# Sheet1.net
KiCad netlist of a schematic drawn in Altium Designer
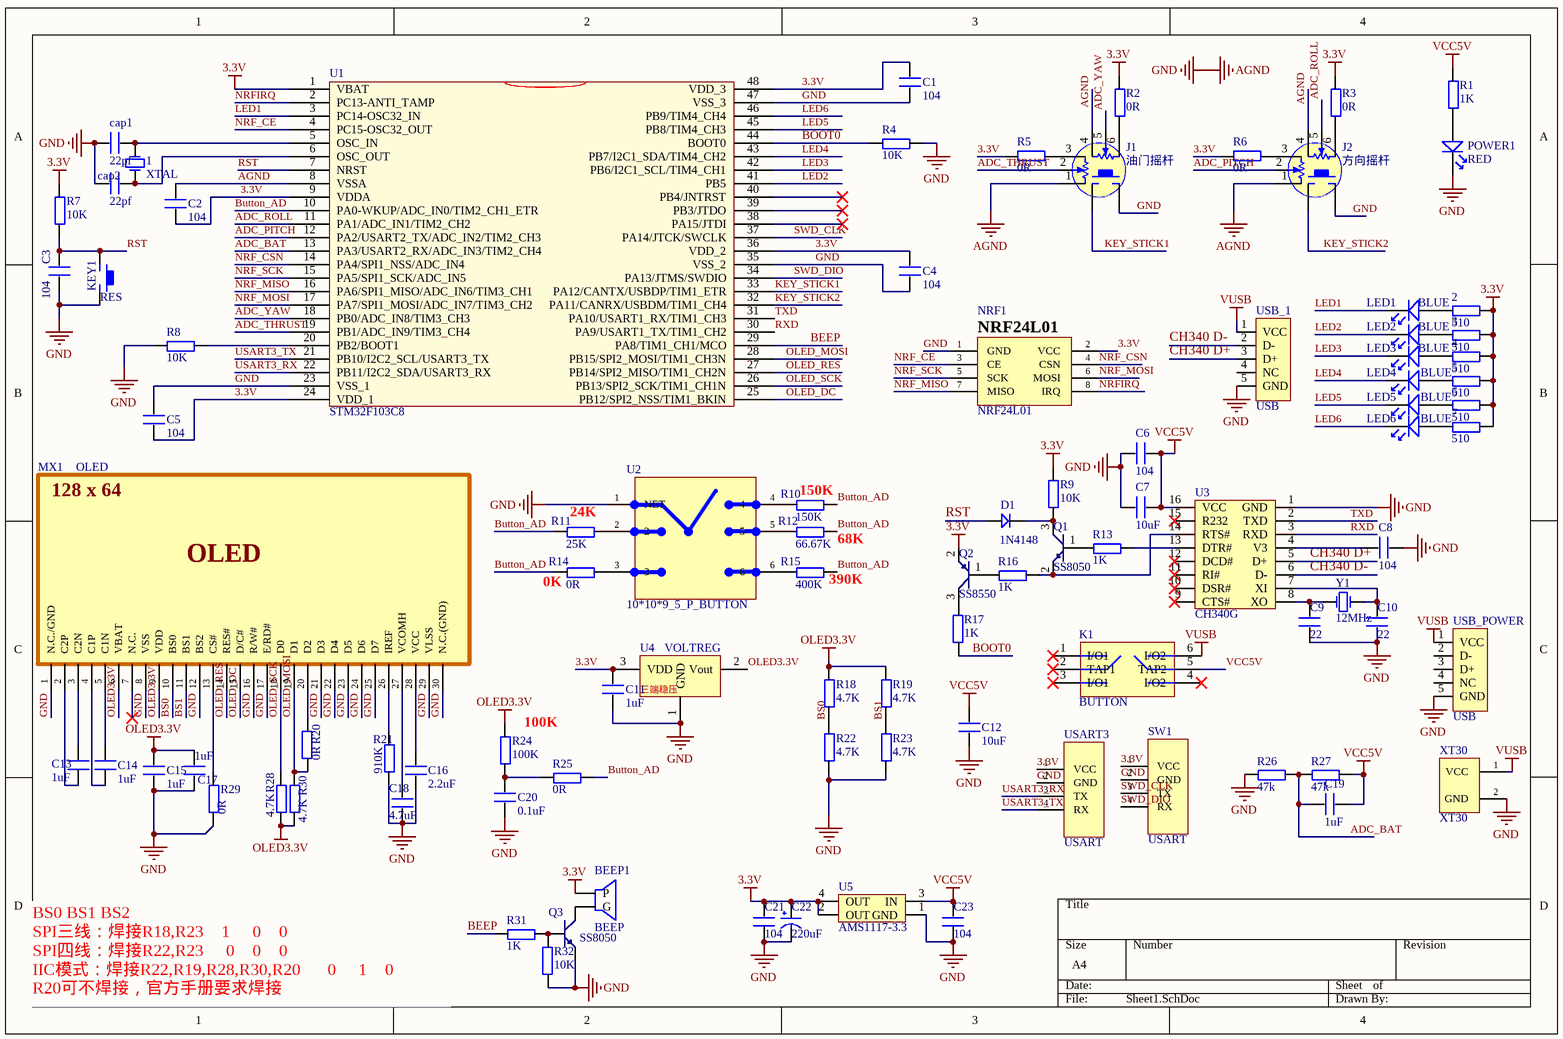
[diagram p0: Sheet1.SchDoc]

(export (version "E")
  (design (tool "Eeschema 10.0.6"))
  (components
    (comp (ref "1") (value "XTAL") (footprint "crystal_Dip") (libsource (lib "REMOTOR V1.6") (part "XTAL")))
    (comp (ref "2") (value "510") (footprint "REMOTOR:0603P") (libsource (lib "REMOTOR V1.6") (part "R")))
    (comp (ref "3") (value "510") (footprint "0603P") (libsource (lib "REMOTOR V1.6") (part "R")))
    (comp (ref "4")
      (value "510")
      (footprint "ATK-2014-09-12:0603P")
      (libsource (lib "REMOTOR V1.6") (part "R"))
    )
    (comp (ref "5")
      (value "510")
      (footprint "ATK-2014-09-12:0603P")
      (libsource (lib "REMOTOR V1.6") (part "R"))
    )
    (comp (ref "6")
      (value "510")
      (footprint "ATK-2014-09-12:0603P")
      (libsource (lib "REMOTOR V1.6") (part "R"))
    )
    (comp (ref "7")
      (value "510")
      (footprint "ATK-2014-09-12:0603P")
      (libsource (lib "REMOTOR V1.6") (part "R"))
    )
    (comp (ref "BEEP1")
      (value "BEEP")
      (footprint "ATK-2014-09-12:BUZZ0.25")
      (libsource (lib "Explorer STM32F407封装库") (part "BEEP"))
    )
    (comp (ref "C1")
      (value "104")
      (footprint "ATK-2014-09-12:0603P")
      (libsource (lib "REMOTOR V1.6") (part "C"))
    )
    (comp (ref "C2")
      (value "104")
      (footprint "ATK-2014-09-12:0603P")
      (libsource (lib "REMOTOR V1.6") (part "C"))
    )
    (comp (ref "C3")
      (value "104")
      (footprint "ATK-2014-09-12:0603P")
      (libsource (lib "REMOTOR V1.6") (part "C"))
    )
    (comp (ref "C4")
      (value "104")
      (footprint "ATK-2014-09-12:0603P")
      (libsource (lib "REMOTOR V1.6") (part "C"))
    )
    (comp (ref "C5")
      (value "104")
      (footprint "ATK-2014-09-12:0603P")
      (libsource (lib "REMOTOR V1.6") (part "C"))
    )
    (comp (ref "C6") (value "104") (footprint "REMOTOR:0603P") (libsource (lib "战舰STM32开发板底板封装库") (part "C")))
    (comp (ref "C7")
      (value "10uF")
      (footprint "REMOTOR:0603P")
      (libsource (lib "战舰STM32开发板底板封装库") (part "C"))
    )
    (comp (ref "C8") (value "104") (footprint "REMOTOR:0603P") (libsource (lib "战舰STM32开发板底板封装库") (part "C")))
    (comp (ref "C9") (value "22") (footprint "REMOTOR:0603P") (libsource (lib "战舰STM32开发板底板封装库") (part "C")))
    (comp (ref "C10") (value "22") (footprint "REMOTOR:0603P") (libsource (lib "战舰STM32开发板底板封装库") (part "C")))
    (comp (ref "C11") (value "1uF") (footprint "REMOTOR:0603P") (libsource (lib "0.96OLED") (part "C")))
    (comp (ref "C12")
      (value "10uF")
      (footprint "REMOTOR:0603P")
      (libsource (lib "战舰STM32开发板底板封装库") (part "C"))
    )
    (comp (ref "C13") (value "1uF") (footprint "REMOTOR:0603P") (libsource (lib "0.96OLED") (part "C")))
    (comp (ref "C14") (value "1uF") (footprint "REMOTOR:0603P") (libsource (lib "0.96OLED") (part "C")))
    (comp (ref "C15") (value "1uF") (footprint "REMOTOR:0603P") (libsource (lib "0.96OLED") (part "C")))
    (comp (ref "C16") (value "2.2uF") (footprint "REMOTOR:0603P") (libsource (lib "0.96OLED") (part "C")))
    (comp (ref "C17") (value "1uF") (footprint "REMOTOR:0603P") (libsource (lib "0.96OLED") (part "C")))
    (comp (ref "C18") (value "4.7uF") (footprint "REMOTOR:0603P") (libsource (lib "0.96OLED") (part "C")))
    (comp (ref "C19") (value "1uF") (footprint "0603P") (libsource (lib "REMOTOR V1.6") (part "C")))
    (comp (ref "C20") (value "0.1uF") (footprint "REMOTOR:0603P") (libsource (lib "0.96OLED") (part "C")))
    (comp (ref "C21")
      (value "104")
      (footprint "REMOTOR:0603P")
      (libsource (lib "Explorer STM32F407封装库") (part "C"))
    )
    (comp (ref "C22")
      (value "220uF")
      (footprint "REMOTOR:C0805 钽电容")
      (libsource (lib "Explorer STM32F407封装库") (part "CAP"))
    )
    (comp (ref "C23")
      (value "104")
      (footprint "REMOTOR:0603P")
      (libsource (lib "Explorer STM32F407封装库") (part "C"))
    )
    (comp (ref "cap1") (value "22pf") (footprint "0603P") (libsource (lib "REMOTOR V1.6") (part "C")))
    (comp (ref "cap2") (value "22pf") (footprint "0603P") (libsource (lib "REMOTOR V1.6") (part "C")))
    (comp (ref "D1")
      (value "1N4148")
      (footprint "ATK-2014-09-12:DIODE_SOP")
      (libsource (lib "战舰STM32开发板底板封装库") (part "D"))
    )
    (comp (ref "J1")
      (value "油门摇杆")
      (footprint "REMOTOR:摇杆2")
      (description "摇杆")
      (libsource (lib "REMOTOR V1.6") (part "摇杆"))
    )
    (comp (ref "J2")
      (value "方向摇杆")
      (footprint "REMOTOR:摇杆2")
      (description "摇杆")
      (libsource (lib "REMOTOR V1.6") (part "摇杆_1"))
    )
    (comp (ref "K1")
      (value "BUTTON")
      (footprint "BTN8*8")
      (description "自锁按键")
      (libsource (lib "REMOTOR V1.6") (part "BUTTON"))
    )
    (comp (ref "KEY1")
      (value "RES")
      (footprint "ATK-2014-09-12:KEY_M")
      (libsource (lib "REMOTOR V1.6") (part "KEY"))
    )
    (comp (ref "LED1") (value "BLUE") (footprint "0805 LED") (libsource (lib "REMOTOR V1.6") (part "LED")))
    (comp (ref "LED2") (value "BLUE") (footprint "0805 LED") (libsource (lib "REMOTOR V1.6") (part "LED")))
    (comp (ref "LED3") (value "BLUE") (footprint "0805 LED") (libsource (lib "REMOTOR V1.6") (part "LED")))
    (comp (ref "LED4") (value "BLUE") (footprint "0805 LED") (libsource (lib "REMOTOR V1.6") (part "LED")))
    (comp (ref "LED5") (value "BLUE") (footprint "0805 LED") (libsource (lib "REMOTOR V1.6") (part "LED")))
    (comp (ref "LED6") (value "BLUE") (footprint "0805 LED") (libsource (lib "REMOTOR V1.6") (part "LED")))
    (comp (ref "MX1") (value "OLED") (footprint "REMOTOR:OLED") (libsource (lib "Chip") (part "OLED")))
    (comp (ref "NRF1")
      (value "NRF24L01")
      (footprint "ATK-2014-09-12:NRF24L01")
      (libsource (lib "REMOTOR V1.6") (part "NRF24L01"))
    )
    (comp (ref "POWER1") (value "RED") (footprint "0805 LED") (libsource (lib "REMOTOR V1.6") (part "LED")))
    (comp (ref "Q1") (value "SS8050") (footprint "REMOTOR:SOT-23-3") (libsource (lib "") (part "SS8050_1")))
    (comp (ref "Q2")
      (value "SS8550")
      (footprint "REMOTOR:SOT-23-3")
      (libsource (lib "ZH_library") (part "SS8550"))
    )
    (comp (ref "Q3")
      (value "SS8050")
      (footprint "REMOTOR:SOT-23-3")
      (libsource (lib "ZH_library") (part "SS8050"))
    )
    (comp (ref "R1")
      (value "1K")
      (footprint "ATK-2014-09-12:0603P")
      (libsource (lib "REMOTOR V1.6") (part "R"))
    )
    (comp (ref "R2")
      (value "0R")
      (footprint "ATK-2014-09-12:0603P")
      (libsource (lib "REMOTOR V1.6") (part "R"))
    )
    (comp (ref "R3")
      (value "0R")
      (footprint "ATK-2014-09-12:0603P")
      (libsource (lib "REMOTOR V1.6") (part "R"))
    )
    (comp (ref "R4")
      (value "10K")
      (footprint "ATK-2014-09-12:0603P")
      (libsource (lib "REMOTOR V1.6") (part "R"))
    )
    (comp (ref "R5")
      (value "0R")
      (footprint "ATK-2014-09-12:0603P")
      (libsource (lib "REMOTOR V1.6") (part "R"))
    )
    (comp (ref "R6")
      (value "0R")
      (footprint "ATK-2014-09-12:0603P")
      (libsource (lib "REMOTOR V1.6") (part "R"))
    )
    (comp (ref "R7")
      (value "10K")
      (footprint "ATK-2014-09-12:0603P")
      (libsource (lib "REMOTOR V1.6") (part "R"))
    )
    (comp (ref "R8")
      (value "10K")
      (footprint "ATK-2014-09-12:0603P")
      (libsource (lib "REMOTOR V1.6") (part "R"))
    )
    (comp (ref "R9") (value "10K") (footprint "REMOTOR:0603P") (libsource (lib "战舰STM32开发板底板封装库") (part "R")))
    (comp (ref "R10") (value "150K") (footprint "REMOTOR:0603P") (libsource (lib "0.96OLED") (part "R")))
    (comp (ref "R11") (value "25K") (footprint "REMOTOR:0603P") (libsource (lib "0.96OLED") (part "R")))
    (comp (ref "R12") (value "66.67K") (footprint "0603P") (libsource (lib "0.96OLED") (part "R")))
    (comp (ref "R13") (value "1K") (footprint "REMOTOR:0603P") (libsource (lib "战舰STM32开发板底板封装库") (part "R")))
    (comp (ref "R14") (value "0R") (footprint "REMOTOR:0603P") (libsource (lib "0.96OLED") (part "R")))
    (comp (ref "R15") (value "400K") (footprint "REMOTOR:0603P") (libsource (lib "0.96OLED") (part "R")))
    (comp (ref "R16") (value "1K") (footprint "REMOTOR:0603P") (libsource (lib "战舰STM32开发板底板封装库") (part "R")))
    (comp (ref "R17") (value "1K") (footprint "REMOTOR:0603P") (libsource (lib "战舰STM32开发板底板封装库") (part "R")))
    (comp (ref "R18") (value "4.7K") (footprint "REMOTOR:0603P") (libsource (lib "0.96OLED") (part "R")))
    (comp (ref "R19") (value "4.7K") (footprint "REMOTOR:0603P") (libsource (lib "0.96OLED") (part "R")))
    (comp (ref "R20") (value "0R") (footprint "REMOTOR:0603P") (libsource (lib "0.96OLED") (part "R")))
    (comp (ref "R21") (value "910K") (footprint "REMOTOR:0603P") (libsource (lib "0.96OLED") (part "R")))
    (comp (ref "R22") (value "4.7K") (footprint "REMOTOR:0603P") (libsource (lib "0.96OLED") (part "R")))
    (comp (ref "R23") (value "4.7K") (footprint "REMOTOR:0603P") (libsource (lib "0.96OLED") (part "R")))
    (comp (ref "R24") (value "100K") (footprint "REMOTOR:0603P") (libsource (lib "0.96OLED") (part "R")))
    (comp (ref "R25") (value "0R") (footprint "REMOTOR:0603P") (libsource (lib "0.96OLED") (part "R")))
    (comp (ref "R26") (value "47k") (footprint "0603P") (libsource (lib "REMOTOR V1.6") (part "R")))
    (comp (ref "R27") (value "47k") (footprint "0603P") (libsource (lib "REMOTOR V1.6") (part "R")))
    (comp (ref "R28") (value "4.7K") (footprint "REMOTOR:0603P") (libsource (lib "0.96OLED") (part "R")))
    (comp (ref "R29") (value "0R") (footprint "REMOTOR:0603P") (libsource (lib "0.96OLED") (part "R")))
    (comp (ref "R30") (value "4.7K") (footprint "REMOTOR:0603P") (libsource (lib "0.96OLED") (part "R")))
    (comp (ref "R31")
      (value "1K")
      (footprint "REMOTOR:0603P")
      (libsource (lib "Explorer STM32F407封装库") (part "R"))
    )
    (comp (ref "R32")
      (value "10K")
      (footprint "REMOTOR:0603P")
      (libsource (lib "Explorer STM32F407封装库") (part "R"))
    )
    (comp (ref "SW1")
      (value "USART")
      (footprint "ATK-2014-09-12:GH1.25-立贴-4P")
      (libsource (lib "REMOTOR V1.6") (part "USART"))
    )
    (comp (ref "U1")
      (value "STM32F103C8")
      (footprint "mTQFP48")
      (libsource (lib "REMOTOR V1.6") (part "STM32F103C6"))
    )
    (comp (ref "U2")
      (value "10*10*9_5_P_BUTTON")
      (footprint "10*10*9_5_P_BUTTON")
      (libsource (lib "Chip") (part "10*10*9_5_P_BUTTON"))
    )
    (comp (ref "U3")
      (value "CH340G")
      (footprint "ATK-2014-09-12:SOP16M")
      (description "USB2UART")
      (libsource (lib "CORE") (part "CH340G"))
    )
    (comp (ref "U4")
      (value "VOLTREG")
      (footprint "REMOTOR:SOT-23-3")
      (description "三端稳压")
      (libsource (lib "Chip") (part "VOLTREG"))
    )
    (comp (ref "U5")
      (value "AMS1117-3.3")
      (footprint "ATK-2014-09-12:AMS1117")
      (libsource (lib "Explorer STM32F407封装库") (part "AMS1117"))
    )
    (comp (ref "USART3")
      (value "USART")
      (footprint "ATK-2014-09-12:HEAD4")
      (libsource (lib "REMOTOR V1.6") (part "USART"))
    )
    (comp (ref "USB_1")
      (value "USB")
      (footprint "ATK-2014-09-12:micro_usb")
      (libsource (lib "Explorer STM32F407封装库") (part "USB5"))
    )
    (comp (ref "USB_POWER")
      (value "USB")
      (footprint "ATK-2014-09-12:micro_usb")
      (libsource (lib "Explorer STM32F407封装库") (part "USB5"))
    )
    (comp (ref "XT30") (value "XT30") (footprint "POWER_2") (libsource (lib "REMOTOR V1.6") (part "XT30")))
    (comp (ref "Y1")
      (value "12MHz")
      (footprint "REMOTOR:crystal_Dip")
      (description "Crystal Oscillator")
      (fields (field (name "PUBLISHER") "Altium Limited"))
      (libsource (lib "战舰STM32开发板底板封装库") (part "XTAL_2"))
    )
  )
  (nets
    (net (code "1") (name "/ADC_BAT") (class "Default")
      (node (ref "C19") (pin "1") (pintype "passive"))
      (node (ref "R26") (pin "2") (pintype "passive"))
      (node (ref "R27") (pin "1") (pintype "passive"))
      (node (ref "U1") (pin "13") (pinfunction "PA3/USART2_RX/ADC_IN3/TIM2_CH4_13") (pintype "passive"))
    )
    (net (code "2") (name "/ADC_PITCH") (class "Default")
      (node (ref "J2") (pin "2") (pinfunction "2_2") (pintype "passive"))
      (node (ref "U1") (pin "12") (pinfunction "PA2/USART2_TX/ADC_IN2/TIM2_CH3_12") (pintype "passive"))
    )
    (net (code "3") (name "/ADC_ROLL") (class "Default")
      (node (ref "J2") (pin "5") (pinfunction "5_5") (pintype "passive"))
      (node (ref "U1") (pin "11") (pinfunction "PA1/ADC_IN1/TIM2_CH2_11") (pintype "passive"))
    )
    (net (code "4") (name "/ADC_THRUST") (class "Default")
      (node (ref "J1") (pin "2") (pinfunction "2_2") (pintype "passive"))
      (node (ref "U1") (pin "19") (pinfunction "PB1/ADC_IN9/TIM3_CH4_19") (pintype "passive"))
    )
    (net (code "5") (name "/ADC_YAW") (class "Default")
      (node (ref "J1") (pin "5") (pinfunction "5_5") (pintype "passive"))
      (node (ref "U1") (pin "18") (pinfunction "PB0/ADC_IN8/TIM3_CH3_18") (pintype "passive"))
    )
    (net (code "6") (name "/BEEP") (class "Default")
      (node (ref "R31") (pin "1") (pintype "passive"))
      (node (ref "U1") (pin "29") (pinfunction "PA8/TIM1_CH1/MCO_29") (pintype "passive"))
    )
    (net (code "7") (name "/BOOT0") (class "Default")
      (node (ref "R17") (pin "2") (pintype "passive"))
      (node (ref "R4") (pin "1") (pintype "passive"))
      (node (ref "U1") (pin "44") (pinfunction "BOOT0_44") (pintype "passive"))
    )
    (net (code "8") (name "/BS0") (class "Default")
      (node (ref "MX1") (pin "10") (pinfunction "BS0_10") (pintype "passive"))
      (node (ref "R18") (pin "1") (pintype "passive"))
      (node (ref "R22") (pin "2") (pintype "passive"))
    )
    (net (code "9") (name "/BS1") (class "Default")
      (node (ref "MX1") (pin "11") (pinfunction "BS1_11") (pintype "passive"))
      (node (ref "R19") (pin "1") (pintype "passive"))
      (node (ref "R23") (pin "2") (pintype "passive"))
    )
    (net (code "10") (name "/Button_AD") (class "Default")
      (node (ref "R10") (pin "2") (pintype "passive"))
      (node (ref "R11") (pin "1") (pintype "passive"))
      (node (ref "R12") (pin "2") (pintype "passive"))
      (node (ref "R14") (pin "1") (pintype "passive"))
      (node (ref "R15") (pin "2") (pintype "passive"))
      (node (ref "R25") (pin "2") (pintype "passive"))
      (node (ref "U1") (pin "10") (pinfunction "PA0-WKUP/ADC_IN0/TIM2_CH1_ETR_10") (pintype "passive"))
    )
    (net (code "11") (name "/CH340 D+") (class "Default")
      (node (ref "U3") (pin "5") (pinfunction "D+_5") (pintype "passive"))
      (node (ref "USB_1") (pin "3") (pinfunction "D+_3") (pintype "passive"))
    )
    (net (code "12") (name "/CH340 D-") (class "Default")
      (node (ref "U3") (pin "6") (pinfunction "D-_6") (pintype "passive"))
      (node (ref "USB_1") (pin "2") (pinfunction "D-_2") (pintype "passive"))
    )
    (net (code "13") (name "/KEY_STICK1") (class "Default")
      (node (ref "J1") (pin "J2") (pinfunction "J2_J2") (pintype "passive"))
      (node (ref "U1") (pin "33") (pinfunction "PA12/CANTX/USBDP/TIM1_ETR_33") (pintype "passive"))
    )
    (net (code "14") (name "/KEY_STICK2") (class "Default")
      (node (ref "J2") (pin "J2") (pinfunction "J2_J2") (pintype "passive"))
      (node (ref "U1") (pin "32") (pinfunction "PA11/CANRX/USBDM/TIM1_CH4_32") (pintype "passive"))
    )
    (net (code "15") (name "/LED1") (class "Default")
      (node (ref "LED1") (pin "2") (pinfunction "2_2") (pintype "passive"))
      (node (ref "U1") (pin "3") (pinfunction "PC14-OSC32_IN_3") (pintype "passive"))
    )
    (net (code "16") (name "/LED2") (class "Default")
      (node (ref "LED2") (pin "2") (pinfunction "2_2") (pintype "passive"))
      (node (ref "U1") (pin "41") (pinfunction "PB5_41") (pintype "passive"))
    )
    (net (code "17") (name "/LED3") (class "Default")
      (node (ref "LED3") (pin "2") (pinfunction "2_2") (pintype "passive"))
      (node (ref "U1") (pin "42") (pinfunction "PB6/I2C1_SCL/TIM4_CH1_42") (pintype "passive"))
    )
    (net (code "18") (name "/LED4") (class "Default")
      (node (ref "LED4") (pin "2") (pinfunction "2_2") (pintype "passive"))
      (node (ref "U1") (pin "43") (pinfunction "PB7/I2C1_SDA/TIM4_CH2_43") (pintype "passive"))
    )
    (net (code "19") (name "/LED5") (class "Default")
      (node (ref "LED5") (pin "2") (pinfunction "2_2") (pintype "passive"))
      (node (ref "U1") (pin "45") (pinfunction "PB8/TIM4_CH3_45") (pintype "passive"))
    )
    (net (code "20") (name "/LED6") (class "Default")
      (node (ref "LED6") (pin "2") (pinfunction "2_2") (pintype "passive"))
      (node (ref "U1") (pin "46") (pinfunction "PB9/TIM4_CH4_46") (pintype "passive"))
    )
    (net (code "21") (name "/NRFIRQ") (class "Default")
      (node (ref "NRF1") (pin "8") (pinfunction "IRQ_8") (pintype "passive"))
      (node (ref "U1") (pin "2") (pinfunction "PC13-ANTI_TAMP_2") (pintype "passive"))
    )
    (net (code "22") (name "/NRF_CE") (class "Default")
      (node (ref "NRF1") (pin "3") (pinfunction "CE_3") (pintype "passive"))
      (node (ref "U1") (pin "4") (pinfunction "PC15-OSC32_OUT_4") (pintype "passive"))
    )
    (net (code "23") (name "/NRF_CSN") (class "Default")
      (node (ref "NRF1") (pin "4") (pinfunction "CSN_4") (pintype "passive"))
      (node (ref "U1") (pin "14") (pinfunction "PA4/SPI1_NSS/ADC_IN4_14") (pintype "passive"))
    )
    (net (code "24") (name "/NRF_MISO") (class "Default")
      (node (ref "NRF1") (pin "7") (pinfunction "MISO_7") (pintype "passive"))
      (node (ref "U1") (pin "16") (pinfunction "PA6/SPI1_MISO/ADC_IN6/TIM3_CH1_16") (pintype "passive"))
    )
    (net (code "25") (name "/NRF_MOSI") (class "Default")
      (node (ref "NRF1") (pin "6") (pinfunction "MOSI_6") (pintype "passive"))
      (node (ref "U1") (pin "17") (pinfunction "PA7/SPI1_MOSI/ADC_IN7/TIM3_CH2_17") (pintype "passive"))
    )
    (net (code "26") (name "/NRF_SCK") (class "Default")
      (node (ref "NRF1") (pin "5") (pinfunction "SCK_5") (pintype "passive"))
      (node (ref "U1") (pin "15") (pinfunction "PA5/SPI1_SCK/ADC_IN5_15") (pintype "passive"))
    )
    (net (code "27") (name "/OLED_DC") (class "Default")
      (node (ref "MX1") (pin "15") (pinfunction "D/C#_15") (pintype "passive"))
      (node (ref "U1") (pin "25") (pinfunction "PB12/SPI2_NSS/TIM1_BKIN_25") (pintype "passive"))
    )
    (net (code "28") (name "/OLED_MOSI") (class "Default")
      (node (ref "MX1") (pin "19") (pinfunction "D1_19") (pintype "passive"))
      (node (ref "R20") (pin "2") (pintype "passive"))
      (node (ref "R30") (pin "2") (pintype "passive"))
      (node (ref "U1") (pin "28") (pinfunction "PB15/SPI2_MOSI/TIM1_CH3N_28") (pintype "passive"))
    )
    (net (code "29") (name "/OLED_RES") (class "Default")
      (node (ref "MX1") (pin "14") (pinfunction "RES#_14") (pintype "passive"))
      (node (ref "U1") (pin "27") (pinfunction "PB14/SPI2_MISO/TIM1_CH2N_27") (pintype "passive"))
    )
    (net (code "30") (name "/OLED_SCK") (class "Default")
      (node (ref "MX1") (pin "18") (pinfunction "D0_18") (pintype "passive"))
      (node (ref "R28") (pin "2") (pintype "passive"))
      (node (ref "U1") (pin "26") (pinfunction "PB13/SPI2_SCK/TIM1_CH1N_26") (pintype "passive"))
    )
    (net (code "31") (name "/RST") (class "Default")
      (node (ref "C3") (pin "2") (pintype "passive"))
      (node (ref "D1") (pin "1") (pintype "passive"))
      (node (ref "KEY1") (pin "1") (pinfunction "1_1") (pintype "passive"))
      (node (ref "R7") (pin "1") (pintype "passive"))
      (node (ref "U1") (pin "7") (pinfunction "NRST_7") (pintype "passive"))
    )
    (net (code "32") (name "/RXD") (class "Default")
      (node (ref "U1") (pin "30") (pinfunction "PA9/USART1_TX/TIM1_CH2_30") (pintype "passive"))
      (node (ref "U3") (pin "3") (pinfunction "RXD_3") (pintype "passive"))
    )
    (net (code "33") (name "/SWD_CLK") (class "Default")
      (node (ref "SW1") (pin "3") (pinfunction "TX_3") (pintype "passive"))
      (node (ref "U1") (pin "37") (pinfunction "PA14/JTCK/SWCLK_37") (pintype "passive"))
    )
    (net (code "34") (name "/SWD_DIO") (class "Default")
      (node (ref "SW1") (pin "4") (pinfunction "RX_4") (pintype "passive"))
      (node (ref "U1") (pin "34") (pinfunction "PA13/JTMS/SWDIO_34") (pintype "passive"))
    )
    (net (code "35") (name "/TXD") (class "Default")
      (node (ref "U1") (pin "31") (pinfunction "PA10/USART1_RX/TIM1_CH3_31") (pintype "passive"))
      (node (ref "U3") (pin "2") (pinfunction "TXD_2") (pintype "passive"))
    )
    (net (code "36") (name "/USART3_RX") (class "Default")
      (node (ref "U1") (pin "22") (pinfunction "PB11/I2C2_SDA/USART3_RX_22") (pintype "passive"))
      (node (ref "USART3") (pin "3") (pinfunction "TX_3") (pintype "passive"))
    )
    (net (code "37") (name "/USART3_TX") (class "Default")
      (node (ref "U1") (pin "21") (pinfunction "PB10/I2C2_SCL/USART3_TX_21") (pintype "passive"))
      (node (ref "USART3") (pin "4") (pinfunction "RX_4") (pintype "passive"))
    )
    (net (code "38") (name "3.3V") (class "Default")
      (node (ref "2") (pin "2") (pintype "passive"))
      (node (ref "3") (pin "2") (pintype "passive"))
      (node (ref "4") (pin "2") (pintype "passive"))
      (node (ref "5") (pin "2") (pintype "passive"))
      (node (ref "6") (pin "2") (pintype "passive"))
      (node (ref "7") (pin "2") (pintype "passive"))
      (node (ref "BEEP1") (pin "1") (pinfunction "P_1") (pintype "passive"))
      (node (ref "C1") (pin "2") (pintype "passive"))
      (node (ref "C11") (pin "2") (pintype "passive"))
      (node (ref "C2") (pin "2") (pintype "passive"))
      (node (ref "C21") (pin "1") (pintype "passive"))
      (node (ref "C22") (pin "1") (pinfunction "VCC_1") (pintype "passive"))
      (node (ref "C4") (pin "2") (pintype "passive"))
      (node (ref "C5") (pin "1") (pintype "passive"))
      (node (ref "NRF1") (pin "2") (pinfunction "VCC_2") (pintype "passive"))
      (node (ref "Q2") (pin "2") (pinfunction "E_2") (pintype "passive"))
      (node (ref "R2") (pin "2") (pintype "passive"))
      (node (ref "R3") (pin "2") (pintype "passive"))
      (node (ref "R5") (pin "2") (pintype "passive"))
      (node (ref "R6") (pin "2") (pintype "passive"))
      (node (ref "R7") (pin "2") (pintype "passive"))
      (node (ref "R9") (pin "1") (pintype "passive"))
      (node (ref "SW1") (pin "1") (pinfunction "VCC_1") (pintype "passive"))
      (node (ref "U1") (pin "1") (pinfunction "VBAT_1") (pintype "passive"))
      (node (ref "U1") (pin "24") (pinfunction "VDD_1_24") (pintype "passive"))
      (node (ref "U1") (pin "36") (pinfunction "VDD_2_36") (pintype "passive"))
      (node (ref "U1") (pin "48") (pinfunction "VDD_3_48") (pintype "passive"))
      (node (ref "U1") (pin "9") (pinfunction "VDDA_9") (pintype "passive"))
      (node (ref "U4") (pin "3") (pinfunction "VDD_3") (pintype "passive"))
      (node (ref "U5") (pin "2") (pinfunction "OUT_2") (pintype "passive"))
      (node (ref "U5") (pin "4") (pinfunction "OUT_4") (pintype "passive"))
      (node (ref "USART3") (pin "1") (pinfunction "VCC_1") (pintype "passive"))
    )
    (net (code "39") (name "AGND") (class "Default")
      (node (ref "C1") (pin "1") (pintype "passive"))
      (node (ref "C10") (pin "1") (pintype "passive"))
      (node (ref "C11") (pin "1") (pintype "passive"))
      (node (ref "C12") (pin "2") (pintype "passive"))
      (node (ref "C15") (pin "1") (pintype "passive"))
      (node (ref "C16") (pin "1") (pintype "passive"))
      (node (ref "C17") (pin "1") (pintype "passive"))
      (node (ref "C18") (pin "1") (pintype "passive"))
      (node (ref "C2") (pin "1") (pintype "passive"))
      (node (ref "C20") (pin "1") (pintype "passive"))
      (node (ref "C21") (pin "2") (pintype "passive"))
      (node (ref "C22") (pin "2") (pinfunction "GND_2") (pintype "passive"))
      (node (ref "C23") (pin "2") (pintype "passive"))
      (node (ref "C3") (pin "1") (pintype "passive"))
      (node (ref "C4") (pin "1") (pintype "passive"))
      (node (ref "C5") (pin "2") (pintype "passive"))
      (node (ref "C6") (pin "2") (pintype "passive"))
      (node (ref "C7") (pin "2") (pintype "passive"))
      (node (ref "C8") (pin "1") (pintype "passive"))
      (node (ref "C9") (pin "1") (pintype "passive"))
      (node (ref "J1") (pin "1") (pinfunction "1_1") (pintype "passive"))
      (node (ref "J1") (pin "4") (pinfunction "4_4") (pintype "passive"))
      (node (ref "J1") (pin "J1") (pinfunction "J1_J1") (pintype "passive"))
      (node (ref "J2") (pin "1") (pinfunction "1_1") (pintype "passive"))
      (node (ref "J2") (pin "4") (pinfunction "4_4") (pintype "passive"))
      (node (ref "J2") (pin "J1") (pinfunction "J1_J1") (pintype "passive"))
      (node (ref "KEY1") (pin "2") (pinfunction "2_2") (pintype "passive"))
      (node (ref "MX1") (pin "1") (pinfunction "N.C./GND_1") (pintype "passive"))
      (node (ref "MX1") (pin "12") (pinfunction "BS2_12") (pintype "passive"))
      (node (ref "MX1") (pin "16") (pinfunction "R/W#_16") (pintype "passive"))
      (node (ref "MX1") (pin "17") (pinfunction "E/RD#_17") (pintype "passive"))
      (node (ref "MX1") (pin "21") (pinfunction "D3_21") (pintype "passive"))
      (node (ref "MX1") (pin "22") (pinfunction "D4_22") (pintype "passive"))
      (node (ref "MX1") (pin "23") (pinfunction "D5_23") (pintype "passive"))
      (node (ref "MX1") (pin "24") (pinfunction "D6_24") (pintype "passive"))
      (node (ref "MX1") (pin "25") (pinfunction "D7_25") (pintype "passive"))
      (node (ref "MX1") (pin "29") (pinfunction "VLSS_29") (pintype "passive"))
      (node (ref "MX1") (pin "30") (pinfunction "N.C.(GND)_30") (pintype "passive"))
      (node (ref "MX1") (pin "8") (pinfunction "VSS_8") (pintype "passive"))
      (node (ref "NRF1") (pin "1") (pinfunction "GND_1") (pintype "passive"))
      (node (ref "POWER1") (pin "2") (pinfunction "2_2") (pintype "passive"))
      (node (ref "Q3") (pin "2") (pinfunction "E_2") (pintype "passive"))
      (node (ref "R21") (pin "1") (pintype "passive"))
      (node (ref "R22") (pin "1") (pintype "passive"))
      (node (ref "R23") (pin "1") (pintype "passive"))
      (node (ref "R26") (pin "1") (pintype "passive"))
      (node (ref "R29") (pin "1") (pintype "passive"))
      (node (ref "R32") (pin "2") (pintype "passive"))
      (node (ref "R4") (pin "2") (pintype "passive"))
      (node (ref "R8") (pin "1") (pintype "passive"))
      (node (ref "SW1") (pin "2") (pinfunction "GND_2") (pintype "passive"))
      (node (ref "U1") (pin "23") (pinfunction "VSS_1_23") (pintype "passive"))
      (node (ref "U1") (pin "35") (pinfunction "VSS_2_35") (pintype "passive"))
      (node (ref "U1") (pin "47") (pinfunction "VSS_3_47") (pintype "passive"))
      (node (ref "U1") (pin "8") (pinfunction "VSSA_8") (pintype "passive"))
      (node (ref "U2") (pin "1") (pinfunction "NET_1") (pintype "passive"))
      (node (ref "U3") (pin "1") (pinfunction "GND_1") (pintype "passive"))
      (node (ref "U4") (pin "1") (pinfunction "GND_1") (pintype "passive"))
      (node (ref "U5") (pin "1") (pinfunction "GND_1") (pintype "passive"))
      (node (ref "USART3") (pin "2") (pinfunction "GND_2") (pintype "passive"))
      (node (ref "USB_1") (pin "5") (pinfunction "GND_5") (pintype "passive"))
      (node (ref "USB_POWER") (pin "5") (pinfunction "GND_5") (pintype "passive"))
      (node (ref "XT30") (pin "2") (pinfunction "GND_2") (pintype "passive"))
      (node (ref "cap1") (pin "2") (pintype "passive"))
      (node (ref "cap2") (pin "2") (pintype "passive"))
    )
    (net (code "40") (name "Net-(1-OSC1)") (class "Default")
      (node (ref "1") (pin "1") (pinfunction "OSC1_1") (pintype "passive"))
      (node (ref "U1") (pin "6") (pinfunction "OSC_OUT_6") (pintype "passive"))
      (node (ref "cap2") (pin "1") (pintype "passive"))
    )
    (net (code "41") (name "Net-(1-OSC2)") (class "Default")
      (node (ref "1") (pin "2") (pinfunction "OSC2_2") (pintype "passive"))
      (node (ref "U1") (pin "5") (pinfunction "OSC_IN_5") (pintype "passive"))
      (node (ref "cap1") (pin "1") (pintype "passive"))
    )
    (net (code "42") (name "Net-(2-Pad1)") (class "Default")
      (node (ref "2") (pin "1") (pintype "passive"))
      (node (ref "LED1") (pin "1") (pinfunction "1_1") (pintype "passive"))
    )
    (net (code "43") (name "Net-(3-Pad1)") (class "Default")
      (node (ref "3") (pin "1") (pintype "passive"))
      (node (ref "LED2") (pin "1") (pinfunction "1_1") (pintype "passive"))
    )
    (net (code "44") (name "Net-(4-Pad1)") (class "Default")
      (node (ref "4") (pin "1") (pintype "passive"))
      (node (ref "LED3") (pin "1") (pinfunction "1_1") (pintype "passive"))
    )
    (net (code "45") (name "Net-(5-Pad1)") (class "Default")
      (node (ref "5") (pin "1") (pintype "passive"))
      (node (ref "LED4") (pin "1") (pinfunction "1_1") (pintype "passive"))
    )
    (net (code "46") (name "Net-(6-Pad1)") (class "Default")
      (node (ref "6") (pin "1") (pintype "passive"))
      (node (ref "LED5") (pin "1") (pinfunction "1_1") (pintype "passive"))
    )
    (net (code "47") (name "Net-(7-Pad1)") (class "Default")
      (node (ref "7") (pin "1") (pintype "passive"))
      (node (ref "LED6") (pin "1") (pinfunction "1_1") (pintype "passive"))
    )
    (net (code "48") (name "Net-(BEEP1-G)") (class "Default")
      (node (ref "BEEP1") (pin "2") (pinfunction "G_2") (pintype "passive"))
      (node (ref "Q3") (pin "3") (pinfunction "C_3") (pintype "passive"))
    )
    (net (code "49") (name "Net-(C20-Pad2)") (class "Default")
      (node (ref "C20") (pin "2") (pintype "passive"))
      (node (ref "R24") (pin "1") (pintype "passive"))
      (node (ref "R25") (pin "1") (pintype "passive"))
    )
    (net (code "50") (name "Net-(J1-Pad3)") (class "Default")
      (node (ref "J1") (pin "3") (pinfunction "3_3") (pintype "passive"))
      (node (ref "R5") (pin "1") (pintype "passive"))
    )
    (net (code "51") (name "Net-(J1-Pad6)") (class "Default")
      (node (ref "J1") (pin "6") (pinfunction "6_6") (pintype "passive"))
      (node (ref "R2") (pin "1") (pintype "passive"))
    )
    (net (code "52") (name "Net-(J2-Pad3)") (class "Default")
      (node (ref "J2") (pin "3") (pinfunction "3_3") (pintype "passive"))
      (node (ref "R6") (pin "1") (pintype "passive"))
    )
    (net (code "53") (name "Net-(J2-Pad6)") (class "Default")
      (node (ref "J2") (pin "6") (pinfunction "6_6") (pintype "passive"))
      (node (ref "R3") (pin "1") (pintype "passive"))
    )
    (net (code "54") (name "Net-(MX1-C1N)") (class "Default")
      (node (ref "C14") (pin "2") (pintype "passive"))
      (node (ref "MX1") (pin "5") (pinfunction "C1N_5") (pintype "passive"))
    )
    (net (code "55") (name "Net-(MX1-C1P)") (class "Default")
      (node (ref "C14") (pin "1") (pintype "passive"))
      (node (ref "MX1") (pin "4") (pinfunction "C1P_4") (pintype "passive"))
    )
    (net (code "56") (name "Net-(MX1-C2N)") (class "Default")
      (node (ref "C13") (pin "2") (pintype "passive"))
      (node (ref "MX1") (pin "3") (pinfunction "C2N_3") (pintype "passive"))
    )
    (net (code "57") (name "Net-(MX1-C2P)") (class "Default")
      (node (ref "C13") (pin "1") (pintype "passive"))
      (node (ref "MX1") (pin "2") (pinfunction "C2P_2") (pintype "passive"))
    )
    (net (code "58") (name "Net-(MX1-CS#)") (class "Default")
      (node (ref "MX1") (pin "13") (pinfunction "CS#_13") (pintype "passive"))
      (node (ref "R29") (pin "2") (pintype "passive"))
    )
    (net (code "59") (name "Net-(MX1-D2)") (class "Default")
      (node (ref "MX1") (pin "20") (pinfunction "D2_20") (pintype "passive"))
      (node (ref "R20") (pin "1") (pintype "passive"))
    )
    (net (code "60") (name "Net-(MX1-IREF)") (class "Default")
      (node (ref "MX1") (pin "26") (pinfunction "IREF_26") (pintype "passive"))
      (node (ref "R21") (pin "2") (pintype "passive"))
    )
    (net (code "61") (name "Net-(MX1-VCC)") (class "Default")
      (node (ref "C16") (pin "2") (pintype "passive"))
      (node (ref "MX1") (pin "28") (pinfunction "VCC_28") (pintype "passive"))
    )
    (net (code "62") (name "Net-(MX1-VCOMH)") (class "Default")
      (node (ref "C18") (pin "2") (pintype "passive"))
      (node (ref "MX1") (pin "27") (pinfunction "VCOMH_27") (pintype "passive"))
    )
    (net (code "63") (name "Net-(POWER1-Pad1)") (class "Default")
      (node (ref "POWER1") (pin "1") (pinfunction "1_1") (pintype "passive"))
      (node (ref "R1") (pin "1") (pintype "passive"))
    )
    (net (code "64") (name "Net-(Q1-B)") (class "Default")
      (node (ref "Q1") (pin "1") (pinfunction "B_1") (pintype "passive"))
      (node (ref "R13") (pin "2") (pintype "passive"))
    )
    (net (code "65") (name "Net-(Q1-C)") (class "Default")
      (node (ref "D1") (pin "2") (pintype "passive"))
      (node (ref "Q1") (pin "3") (pinfunction "C_3") (pintype "passive"))
      (node (ref "R9") (pin "2") (pintype "passive"))
    )
    (net (code "66") (name "Net-(Q1-E)") (class "Default")
      (node (ref "Q1") (pin "2") (pinfunction "E_2") (pintype "passive"))
      (node (ref "R16") (pin "1") (pintype "passive"))
      (node (ref "U3") (pin "14") (pinfunction "RTS#_14") (pintype "passive"))
    )
    (net (code "67") (name "Net-(Q2-B)") (class "Default")
      (node (ref "Q2") (pin "1") (pinfunction "B_1") (pintype "passive"))
      (node (ref "R16") (pin "2") (pintype "passive"))
    )
    (net (code "68") (name "Net-(Q2-C)") (class "Default")
      (node (ref "Q2") (pin "3") (pinfunction "C_3") (pintype "passive"))
      (node (ref "R17") (pin "1") (pintype "passive"))
    )
    (net (code "69") (name "Net-(Q3-B)") (class "Default")
      (node (ref "Q3") (pin "1") (pinfunction "B_1") (pintype "passive"))
      (node (ref "R31") (pin "2") (pintype "passive"))
      (node (ref "R32") (pin "1") (pintype "passive"))
    )
    (net (code "70") (name "Net-(R10-Pad1)") (class "Default")
      (node (ref "R10") (pin "1") (pintype "passive"))
      (node (ref "U2") (pin "4") (pinfunction "4_4") (pintype "passive"))
    )
    (net (code "71") (name "Net-(R11-Pad2)") (class "Default")
      (node (ref "R11") (pin "2") (pintype "passive"))
      (node (ref "U2") (pin "2") (pinfunction "2_2") (pintype "passive"))
    )
    (net (code "72") (name "Net-(R12-Pad1)") (class "Default")
      (node (ref "R12") (pin "1") (pintype "passive"))
      (node (ref "U2") (pin "5") (pinfunction "5_5") (pintype "passive"))
    )
    (net (code "73") (name "Net-(R14-Pad2)") (class "Default")
      (node (ref "R14") (pin "2") (pintype "passive"))
      (node (ref "U2") (pin "3") (pinfunction "3_3") (pintype "passive"))
    )
    (net (code "74") (name "Net-(R15-Pad1)") (class "Default")
      (node (ref "R15") (pin "1") (pintype "passive"))
      (node (ref "U2") (pin "6") (pinfunction "6_6") (pintype "passive"))
    )
    (net (code "75") (name "Net-(U1-PB2{slash}BOOT1)") (class "Default")
      (node (ref "R8") (pin "2") (pintype "passive"))
      (node (ref "U1") (pin "20") (pinfunction "PB2/BOOT1_20") (pintype "passive"))
    )
    (net (code "76") (name "Net-(U3-DTR#)") (class "Default")
      (node (ref "R13") (pin "1") (pintype "passive"))
      (node (ref "U3") (pin "13") (pinfunction "DTR#_13") (pintype "passive"))
    )
    (net (code "77") (name "Net-(U3-V3)") (class "Default")
      (node (ref "C8") (pin "2") (pintype "passive"))
      (node (ref "U3") (pin "4") (pinfunction "V3_4") (pintype "passive"))
    )
    (net (code "78") (name "Net-(U3-XI)") (class "Default")
      (node (ref "C10") (pin "2") (pintype "passive"))
      (node (ref "U3") (pin "7") (pinfunction "XI_7") (pintype "passive"))
      (node (ref "Y1") (pin "1") (pinfunction "OSC1_1") (pintype "passive"))
    )
    (net (code "79") (name "Net-(U3-XO)") (class "Default")
      (node (ref "C9") (pin "2") (pintype "passive"))
      (node (ref "U3") (pin "8") (pinfunction "XO_8") (pintype "passive"))
      (node (ref "Y1") (pin "2") (pinfunction "OSC2_2") (pintype "passive"))
    )
    (net (code "80") (name "OLED3.3V") (class "Default")
      (node (ref "C15") (pin "2") (pintype "passive"))
      (node (ref "C17") (pin "2") (pintype "passive"))
      (node (ref "MX1") (pin "6") (pinfunction "VBAT_6") (pintype "passive"))
      (node (ref "MX1") (pin "9") (pinfunction "VDD_9") (pintype "passive"))
      (node (ref "R18") (pin "2") (pintype "passive"))
      (node (ref "R19") (pin "2") (pintype "passive"))
      (node (ref "R24") (pin "2") (pintype "passive"))
      (node (ref "R28") (pin "1") (pintype "passive"))
      (node (ref "R30") (pin "1") (pintype "passive"))
      (node (ref "U4") (pin "2") (pinfunction "Vout_2") (pintype "passive"))
    )
    (net (code "81") (name "VCC5V") (class "Default")
      (node (ref "C12") (pin "1") (pintype "passive"))
      (node (ref "C19") (pin "2") (pintype "passive"))
      (node (ref "C23") (pin "1") (pintype "passive"))
      (node (ref "C6") (pin "1") (pintype "passive"))
      (node (ref "C7") (pin "1") (pintype "passive"))
      (node (ref "K1") (pin "5") (pinfunction "TAP2_5") (pintype "passive"))
      (node (ref "R1") (pin "2") (pintype "passive"))
      (node (ref "R27") (pin "2") (pintype "passive"))
      (node (ref "U3") (pin "16") (pinfunction "VCC_16") (pintype "passive"))
      (node (ref "U5") (pin "3") (pinfunction "IN_3") (pintype "passive"))
    )
    (net (code "82") (name "VUSB") (class "Default")
      (node (ref "K1") (pin "6") (pinfunction "I/O2_6") (pintype "passive"))
      (node (ref "USB_1") (pin "1") (pinfunction "VCC_1") (pintype "passive"))
      (node (ref "USB_POWER") (pin "1") (pinfunction "VCC_1") (pintype "passive"))
      (node (ref "XT30") (pin "1") (pinfunction "VCC_1") (pintype "passive"))
    )
    (net (code "83") (name "unconnected-(K1-I{slash}O1-Pad1)") (class "Default")
      (node (ref "K1") (pin "1") (pinfunction "I/O1_1") (pintype "passive+no_connect"))
    )
    (net (code "84") (name "unconnected-(K1-I{slash}O1-Pad3)") (class "Default")
      (node (ref "K1") (pin "3") (pinfunction "I/O1_3") (pintype "passive+no_connect"))
    )
    (net (code "85") (name "unconnected-(K1-I{slash}O2-Pad4)") (class "Default")
      (node (ref "K1") (pin "4") (pinfunction "I/O2_4") (pintype "passive+no_connect"))
    )
    (net (code "86") (name "unconnected-(K1-TAP1-Pad2)") (class "Default")
      (node (ref "K1") (pin "2") (pinfunction "TAP1_2") (pintype "passive+no_connect"))
    )
    (net (code "87") (name "unconnected-(MX1-N.C.-Pad7)") (class "Default")
      (node (ref "MX1") (pin "7") (pinfunction "N.C._7") (pintype "passive+no_connect"))
    )
    (net (code "88") (name "unconnected-(U1-PA15{slash}JTDI-Pad38)") (class "Default")
      (node (ref "U1") (pin "38") (pinfunction "PA15/JTDI_38") (pintype "passive+no_connect"))
    )
    (net (code "89") (name "unconnected-(U1-PB3{slash}JTDO-Pad39)") (class "Default")
      (node (ref "U1") (pin "39") (pinfunction "PB3/JTDO_39") (pintype "passive+no_connect"))
    )
    (net (code "90") (name "unconnected-(U1-PB4{slash}JNTRST-Pad40)") (class "Default")
      (node (ref "U1") (pin "40") (pinfunction "PB4/JNTRST_40") (pintype "passive+no_connect"))
    )
    (net (code "91") (name "unconnected-(U3-CTS#-Pad9)") (class "Default")
      (node (ref "U3") (pin "9") (pinfunction "CTS#_9") (pintype "passive+no_connect"))
    )
    (net (code "92") (name "unconnected-(U3-DCD#-Pad12)") (class "Default")
      (node (ref "U3") (pin "12") (pinfunction "DCD#_12") (pintype "passive+no_connect"))
    )
    (net (code "93") (name "unconnected-(U3-DSR#-Pad10)") (class "Default")
      (node (ref "U3") (pin "10") (pinfunction "DSR#_10") (pintype "passive+no_connect"))
    )
    (net (code "94") (name "unconnected-(U3-R232-Pad15)") (class "Default")
      (node (ref "U3") (pin "15") (pinfunction "R232_15") (pintype "passive+no_connect"))
    )
    (net (code "95") (name "unconnected-(U3-RI#-Pad11)") (class "Default")
      (node (ref "U3") (pin "11") (pinfunction "RI#_11") (pintype "passive+no_connect"))
    )
    (net (code "96") (name "unconnected-(USB_1-NC-Pad4)") (class "Default")
      (node (ref "USB_1") (pin "4") (pinfunction "NC_4") (pintype "passive"))
    )
    (net (code "97") (name "unconnected-(USB_POWER-D+-Pad3)") (class "Default")
      (node (ref "USB_POWER") (pin "3") (pinfunction "D+_3") (pintype "passive"))
    )
    (net (code "98") (name "unconnected-(USB_POWER-D--Pad2)") (class "Default")
      (node (ref "USB_POWER") (pin "2") (pinfunction "D-_2") (pintype "passive"))
    )
    (net (code "99") (name "unconnected-(USB_POWER-NC-Pad4)") (class "Default")
      (node (ref "USB_POWER") (pin "4") (pinfunction "NC_4") (pintype "passive"))
    )
  )
)
